# battery_monitor_6803-2_-no_uno.net
KiCad netlist of a schematic drawn in EAGLE
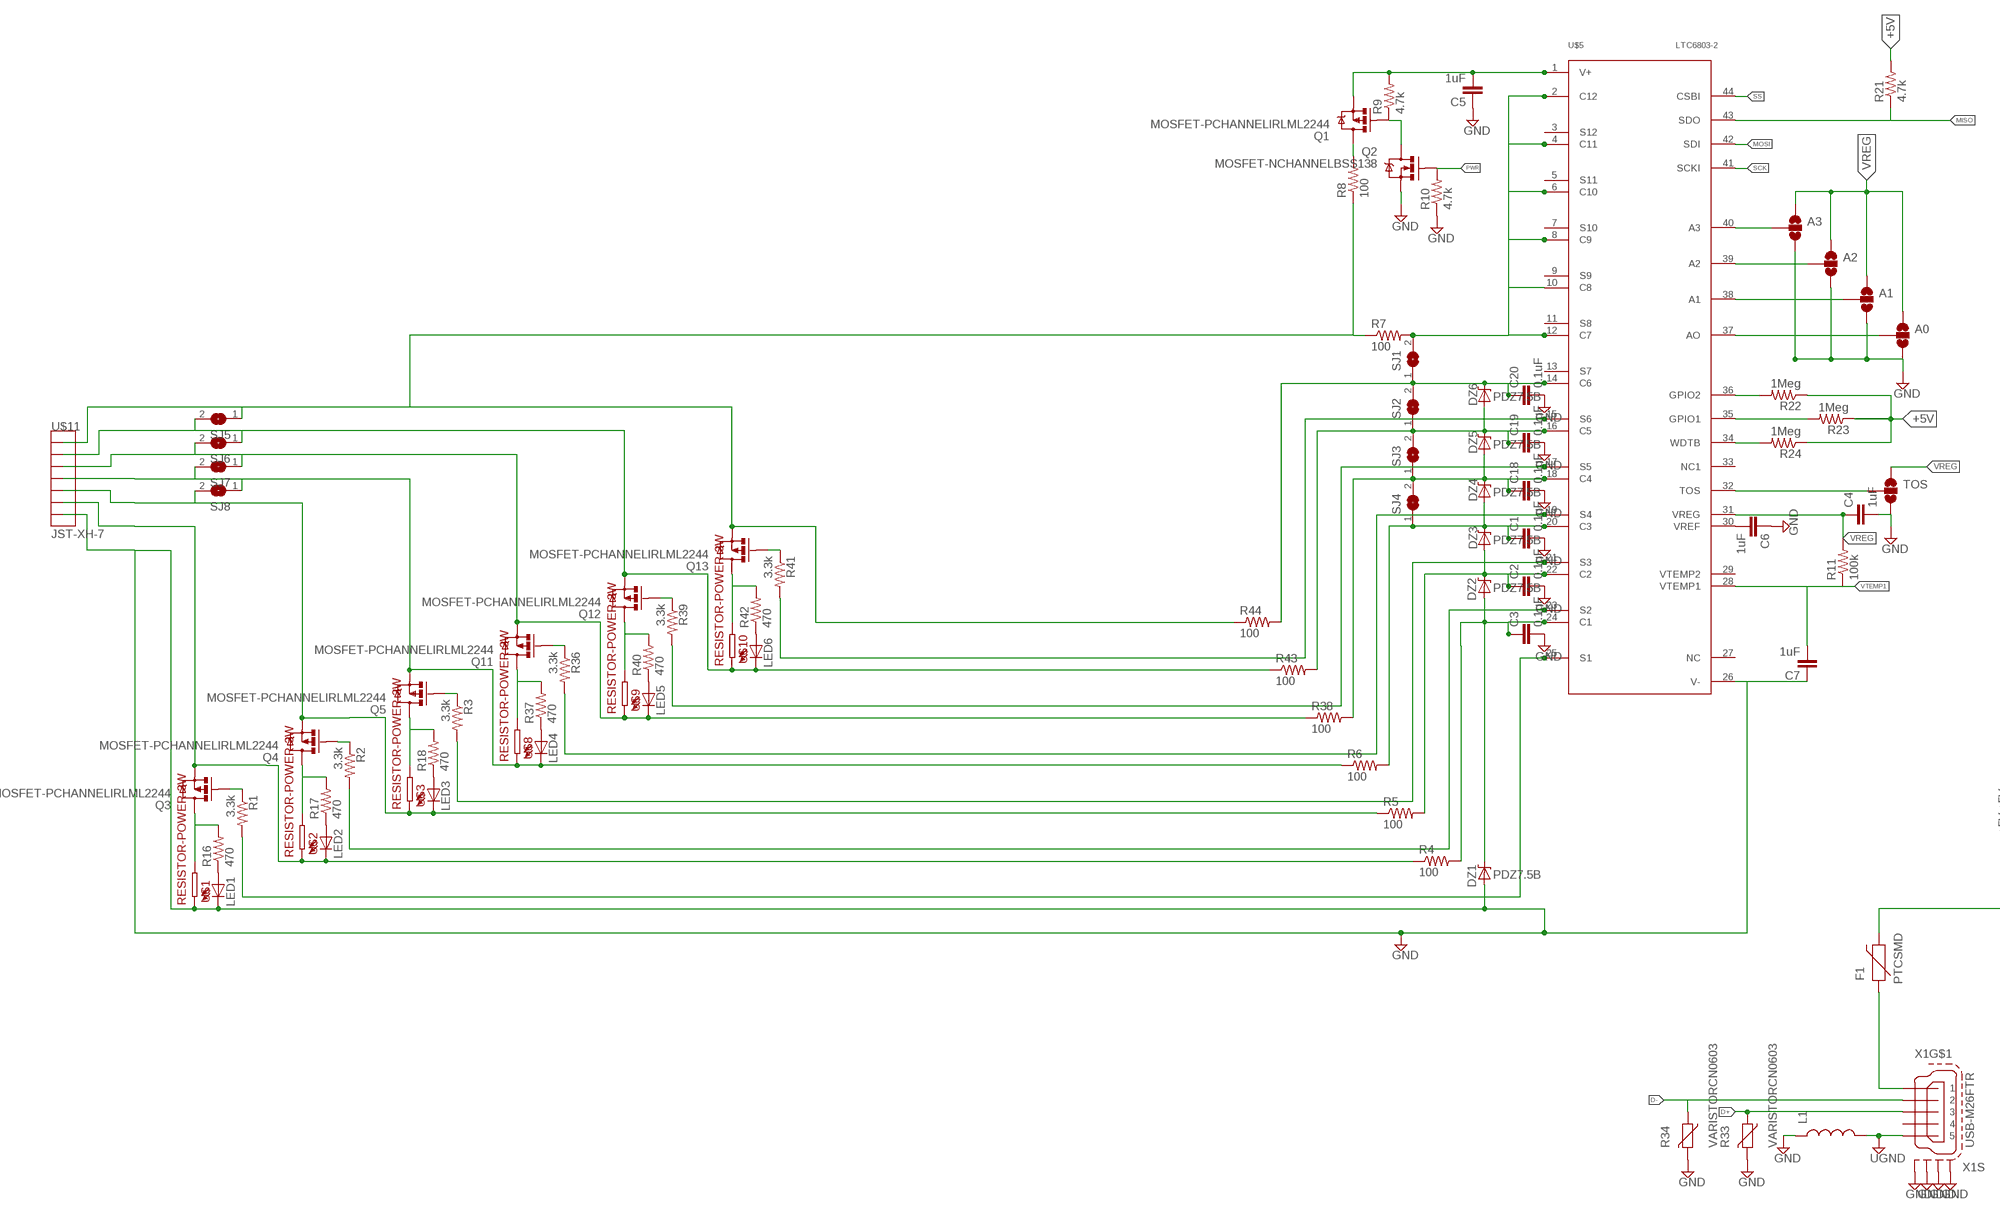
[diagram p0: schematic, sheet 1, part 1 of 2]
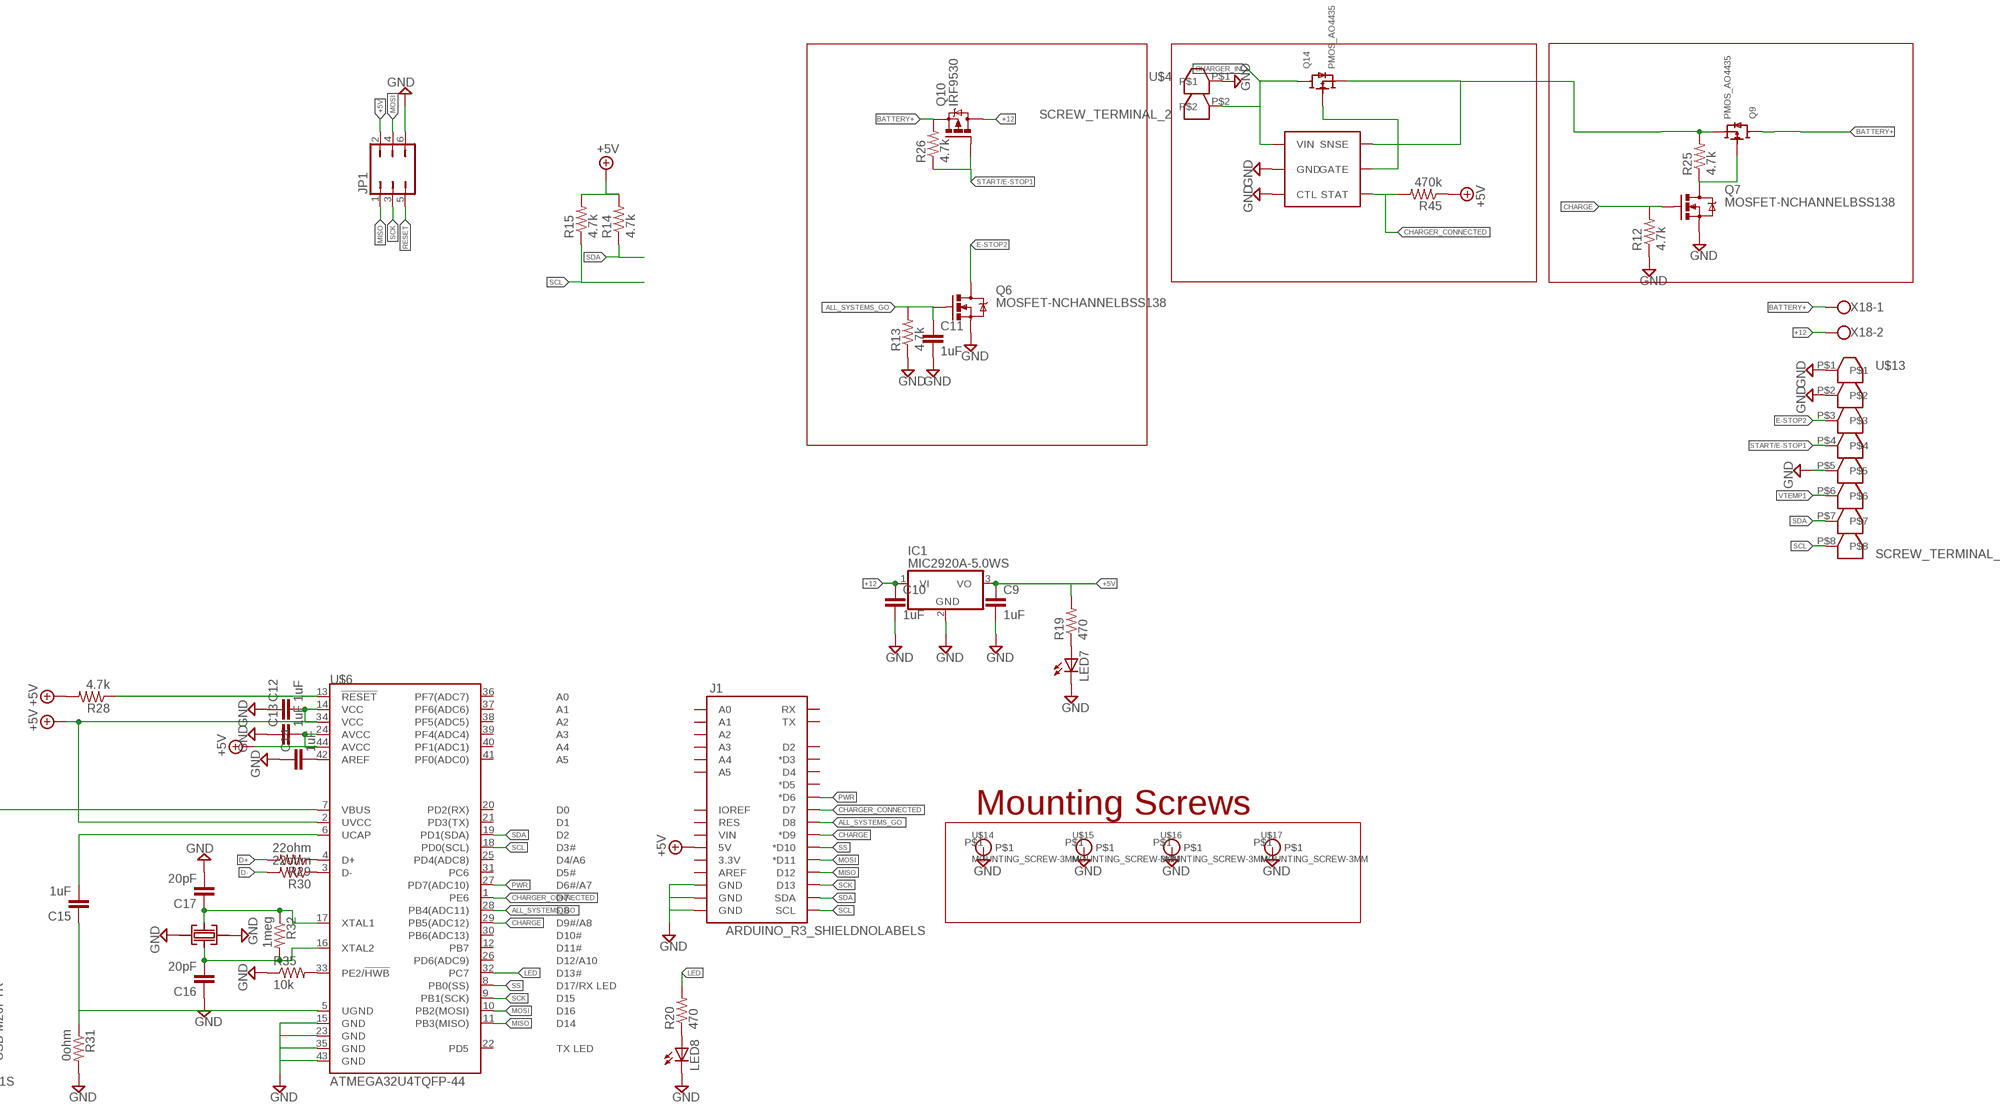
[diagram p1: schematic, sheet 1, part 2 of 2]

(export (version "E")
  (design (tool "Eeschema 10.0.6"))
  (components
    (comp (ref "A0")
      (value "SOLDERJUMPER_2WAYS")
      (footprint "eagle-import:SJ_3")
      (libsource (lib "eagle-import") (part "SOLDERJUMPER_2WAYS"))
    )
    (comp (ref "A1")
      (value "SOLDERJUMPER_2WAYS")
      (footprint "eagle-import:SJ_3")
      (libsource (lib "eagle-import") (part "SOLDERJUMPER_2WAYS"))
    )
    (comp (ref "A2")
      (value "SOLDERJUMPER_2WAYS")
      (footprint "eagle-import:SJ_3")
      (libsource (lib "eagle-import") (part "SOLDERJUMPER_2WAYS"))
    )
    (comp (ref "A3")
      (value "SOLDERJUMPER_2WAYS")
      (footprint "eagle-import:SJ_3")
      (libsource (lib "eagle-import") (part "SOLDERJUMPER_2WAYS"))
    )
    (comp (ref "C1")
      (value "0.1uF")
      (footprint "eagle-import:0603-CAP")
      (libsource (lib "eagle-import") (part "0.1UF-100V-10%(0603)"))
    )
    (comp (ref "C2")
      (value "0.1uF")
      (footprint "eagle-import:0603-CAP")
      (libsource (lib "eagle-import") (part "0.1UF-100V-10%(0603)"))
    )
    (comp (ref "C3")
      (value "0.1uF")
      (footprint "eagle-import:0603-CAP")
      (libsource (lib "eagle-import") (part "0.1UF-100V-10%(0603)"))
    )
    (comp (ref "C4")
      (value "1uF")
      (footprint "eagle-import:0603-CAP")
      (fields (field (name "PROD_ID") "CAP-08390"))
      (libsource (lib "eagle-import") (part "0.1UF-100V-10%(0603)"))
    )
    (comp (ref "C5")
      (value "1uF")
      (footprint "eagle-import:0603-CAP")
      (fields (field (name "PROD_ID") "CAP-08390"))
      (libsource (lib "eagle-import") (part "0.1UF-100V-10%(0603)"))
    )
    (comp (ref "C6")
      (value "1uF")
      (footprint "eagle-import:0603-CAP")
      (fields (field (name "PROD_ID") "CAP-08390"))
      (libsource (lib "eagle-import") (part "0.1UF-100V-10%(0603)"))
    )
    (comp (ref "C7")
      (value "1uF")
      (footprint "eagle-import:0603-CAP")
      (fields (field (name "PROD_ID") "CAP-08390"))
      (libsource (lib "eagle-import") (part "0.1UF-100V-10%(0603)"))
    )
    (comp (ref "C9")
      (value "1uF")
      (footprint "eagle-import:0603-CAP")
      (fields (field (name "PROD_ID") "CAP-08390"))
      (libsource (lib "eagle-import") (part "0.1UF-100V-10%(0603)"))
    )
    (comp (ref "C10")
      (value "1uF")
      (footprint "eagle-import:0603-CAP")
      (fields (field (name "PROD_ID") "CAP-08390"))
      (libsource (lib "eagle-import") (part "0.1UF-100V-10%(0603)"))
    )
    (comp (ref "C11")
      (value "1uF")
      (footprint "eagle-import:0603-CAP")
      (fields (field (name "PROD_ID") "CAP-08390"))
      (libsource (lib "eagle-import") (part "0.1UF-100V-10%(0603)"))
    )
    (comp (ref "C12")
      (value "1uF")
      (footprint "eagle-import:0603-CAP")
      (fields (field (name "PROD_ID") "CAP-08390"))
      (libsource (lib "eagle-import") (part "0.1UF-100V-10%(0603)"))
    )
    (comp (ref "C13")
      (value "1uF")
      (footprint "eagle-import:0603-CAP")
      (fields (field (name "PROD_ID") "CAP-08390"))
      (libsource (lib "eagle-import") (part "0.1UF-100V-10%(0603)"))
    )
    (comp (ref "C14")
      (value "1uF")
      (footprint "eagle-import:0603-CAP")
      (fields (field (name "PROD_ID") "CAP-08390"))
      (libsource (lib "eagle-import") (part "0.1UF-100V-10%(0603)"))
    )
    (comp (ref "C15")
      (value "1uF")
      (footprint "eagle-import:0603-CAP")
      (fields (field (name "PROD_ID") "CAP-08390"))
      (libsource (lib "eagle-import") (part "0.1UF-100V-10%(0603)"))
    )
    (comp (ref "C16")
      (value "20pF")
      (footprint "eagle-import:0603-CAP")
      (fields (field (name "PROD_ID") "CAP-08390"))
      (libsource (lib "eagle-import") (part "0.1UF-100V-10%(0603)"))
    )
    (comp (ref "C17")
      (value "20pF")
      (footprint "eagle-import:0603-CAP")
      (fields (field (name "PROD_ID") "CAP-08390"))
      (libsource (lib "eagle-import") (part "0.1UF-100V-10%(0603)"))
    )
    (comp (ref "C18")
      (value "0.1uF")
      (footprint "eagle-import:0603-CAP")
      (fields (field (name "PROD_ID") "CAP-08390"))
      (libsource (lib "eagle-import") (part "0.1UF-100V-10%(0603)"))
    )
    (comp (ref "C19")
      (value "0.1uF")
      (footprint "eagle-import:0603-CAP")
      (fields (field (name "PROD_ID") "CAP-08390"))
      (libsource (lib "eagle-import") (part "0.1UF-100V-10%(0603)"))
    )
    (comp (ref "C20")
      (value "0.1uF")
      (footprint "eagle-import:0603-CAP")
      (fields (field (name "PROD_ID") "CAP-08390"))
      (libsource (lib "eagle-import") (part "0.1UF-100V-10%(0603)"))
    )
    (comp (ref "DZ1")
      (value "PDZ7.5B")
      (footprint "eagle-import:SOD-323")
      (libsource (lib "eagle-import") (part "DIODE-ZENER-BZT52"))
    )
    (comp (ref "DZ2")
      (value "PDZ7.5B")
      (footprint "eagle-import:SOD-323")
      (libsource (lib "eagle-import") (part "DIODE-ZENER-BZT52"))
    )
    (comp (ref "DZ3")
      (value "PDZ7.5B")
      (footprint "eagle-import:SOD-323")
      (libsource (lib "eagle-import") (part "DIODE-ZENER-BZT52"))
    )
    (comp (ref "DZ4")
      (value "PDZ7.5B")
      (footprint "eagle-import:SOD-323")
      (libsource (lib "eagle-import") (part "DIODE-ZENER-BZT52"))
    )
    (comp (ref "DZ5")
      (value "PDZ7.5B")
      (footprint "eagle-import:SOD-323")
      (libsource (lib "eagle-import") (part "DIODE-ZENER-BZT52"))
    )
    (comp (ref "DZ6")
      (value "PDZ7.5B")
      (footprint "eagle-import:SOD-323")
      (libsource (lib "eagle-import") (part "DIODE-ZENER-BZT52"))
    )
    (comp (ref "F1")
      (value "PTCSMD")
      (footprint "eagle-import:PTC-1206")
      (libsource (lib "eagle-import") (part "PTCSMD"))
    )
    (comp (ref "IC1")
      (value "MIC2920A-5.0WS")
      (footprint "eagle-import:SOT223")
      (libsource (lib "eagle-import") (part "MCP1703DB"))
    )
    (comp (ref "J1")
      (value "ARDUINO_R3_SHIELDNOLABELS")
      (footprint "eagle-import:UNO_R3_SHIELD_NOLABELS")
      (libsource (lib "eagle-import") (part "ARDUINO_R3_SHIELDNOLABELS"))
    )
    (comp (ref "JP1")
      (value "JP3Q")
      (footprint "eagle-import:JP3Q")
      (libsource (lib "eagle-import") (part "JP3Q"))
    )
    (comp (ref "L1")
      (value "INDUCTOR0805")
      (footprint "eagle-import:0805")
      (libsource (lib "eagle-import") (part "INDUCTOR0805"))
    )
    (comp (ref "LED1")
      (value "LED0603")
      (footprint "eagle-import:LED-0603")
      (libsource (lib "eagle-import") (part "LED0603"))
    )
    (comp (ref "LED2")
      (value "LED0603")
      (footprint "eagle-import:LED-0603")
      (libsource (lib "eagle-import") (part "LED0603"))
    )
    (comp (ref "LED3")
      (value "LED0603")
      (footprint "eagle-import:LED-0603")
      (libsource (lib "eagle-import") (part "LED0603"))
    )
    (comp (ref "LED4")
      (value "LED0603")
      (footprint "eagle-import:LED-0603")
      (libsource (lib "eagle-import") (part "LED0603"))
    )
    (comp (ref "LED5")
      (value "LED0603")
      (footprint "eagle-import:LED-0603")
      (libsource (lib "eagle-import") (part "LED0603"))
    )
    (comp (ref "LED6")
      (value "LED0603")
      (footprint "eagle-import:LED-0603")
      (libsource (lib "eagle-import") (part "LED0603"))
    )
    (comp (ref "LED7")
      (value "LED0603")
      (footprint "eagle-import:LED-0603")
      (libsource (lib "eagle-import") (part "LED0603"))
    )
    (comp (ref "LED8")
      (value "LED0603")
      (footprint "eagle-import:LED-0603")
      (libsource (lib "eagle-import") (part "LED0603"))
    )
    (comp (ref "Q1")
      (value "MOSFET-PCHANNELIRLML2244")
      (footprint "eagle-import:SOT23-3")
      (libsource (lib "eagle-import") (part "MOSFET-PCHANNELIRLML2244"))
    )
    (comp (ref "Q2")
      (value "MOSFET-NCHANNELBSS138")
      (footprint "eagle-import:SOT23")
      (libsource (lib "eagle-import") (part "MOSFET-NCHANNELBSS138"))
    )
    (comp (ref "Q3")
      (value "MOSFET-PCHANNELIRLML2244")
      (footprint "eagle-import:SOT23-3")
      (libsource (lib "eagle-import") (part "MOSFET-PCHANNELIRLML2244"))
    )
    (comp (ref "Q4")
      (value "MOSFET-PCHANNELIRLML2244")
      (footprint "eagle-import:SOT23-3")
      (libsource (lib "eagle-import") (part "MOSFET-PCHANNELIRLML2244"))
    )
    (comp (ref "Q5")
      (value "MOSFET-PCHANNELIRLML2244")
      (footprint "eagle-import:SOT23-3")
      (libsource (lib "eagle-import") (part "MOSFET-PCHANNELIRLML2244"))
    )
    (comp (ref "Q6")
      (value "MOSFET-NCHANNELBSS138")
      (footprint "eagle-import:SOT23")
      (libsource (lib "eagle-import") (part "MOSFET-NCHANNELBSS138"))
    )
    (comp (ref "Q7")
      (value "MOSFET-NCHANNELBSS138")
      (footprint "eagle-import:SOT23")
      (libsource (lib "eagle-import") (part "MOSFET-NCHANNELBSS138"))
    )
    (comp (ref "Q9")
      (value "PMOS_AO4435")
      (footprint "eagle-import:SOIC8")
      (libsource (lib "eagle-import") (part "PMOS_AO4435"))
    )
    (comp (ref "Q10")
      (value "IRF9530")
      (footprint "eagle-import:TO220BV")
      (libsource (lib "eagle-import") (part "IRF9530"))
    )
    (comp (ref "Q11")
      (value "MOSFET-PCHANNELIRLML2244")
      (footprint "eagle-import:SOT23-3")
      (libsource (lib "eagle-import") (part "MOSFET-PCHANNELIRLML2244"))
    )
    (comp (ref "Q12")
      (value "MOSFET-PCHANNELIRLML2244")
      (footprint "eagle-import:SOT23-3")
      (libsource (lib "eagle-import") (part "MOSFET-PCHANNELIRLML2244"))
    )
    (comp (ref "Q13")
      (value "MOSFET-PCHANNELIRLML2244")
      (footprint "eagle-import:SOT23-3")
      (libsource (lib "eagle-import") (part "MOSFET-PCHANNELIRLML2244"))
    )
    (comp (ref "Q14")
      (value "PMOS_AO4435")
      (footprint "eagle-import:SOIC8")
      (libsource (lib "eagle-import") (part "PMOS_AO4435"))
    )
    (comp (ref "R1")
      (value "3.3k")
      (footprint "eagle-import:0603-RES")
      (libsource (lib "eagle-import") (part "3.3KOHM1/10W1%(0603)"))
    )
    (comp (ref "R2")
      (value "3.3k")
      (footprint "eagle-import:0603-RES")
      (libsource (lib "eagle-import") (part "3.3KOHM1/10W1%(0603)"))
    )
    (comp (ref "R3")
      (value "3.3k")
      (footprint "eagle-import:0603-RES")
      (libsource (lib "eagle-import") (part "3.3KOHM1/10W1%(0603)"))
    )
    (comp (ref "R4")
      (value "100")
      (footprint "eagle-import:0603-RES")
      (libsource (lib "eagle-import") (part "3.3KOHM1/10W1%(0603)"))
    )
    (comp (ref "R5")
      (value "100")
      (footprint "eagle-import:0603-RES")
      (libsource (lib "eagle-import") (part "3.3KOHM1/10W1%(0603)"))
    )
    (comp (ref "R6")
      (value "100")
      (footprint "eagle-import:0603-RES")
      (libsource (lib "eagle-import") (part "3.3KOHM1/10W1%(0603)"))
    )
    (comp (ref "R7")
      (value "100")
      (footprint "eagle-import:0603-RES")
      (libsource (lib "eagle-import") (part "3.3KOHM1/10W1%(0603)"))
    )
    (comp (ref "R8")
      (value "100")
      (footprint "eagle-import:0603-RES")
      (libsource (lib "eagle-import") (part "3.3KOHM1/10W1%(0603)"))
    )
    (comp (ref "R9")
      (value "4.7k")
      (footprint "eagle-import:0603-RES")
      (libsource (lib "eagle-import") (part "3.3KOHM1/10W1%(0603)"))
    )
    (comp (ref "R10")
      (value "4.7k")
      (footprint "eagle-import:0603-RES")
      (libsource (lib "eagle-import") (part "3.3KOHM1/10W1%(0603)"))
    )
    (comp (ref "R11")
      (value "100k")
      (footprint "eagle-import:0603-RES")
      (libsource (lib "eagle-import") (part "3.3KOHM1/10W1%(0603)"))
    )
    (comp (ref "R12")
      (value "4.7k")
      (footprint "eagle-import:0603-RES")
      (libsource (lib "eagle-import") (part "3.3KOHM1/10W1%(0603)"))
    )
    (comp (ref "R13")
      (value "4.7k")
      (footprint "eagle-import:0603-RES")
      (libsource (lib "eagle-import") (part "3.3KOHM1/10W1%(0603)"))
    )
    (comp (ref "R14")
      (value "4.7k")
      (footprint "eagle-import:0603-RES")
      (libsource (lib "eagle-import") (part "3.3KOHM1/10W1%(0603)"))
    )
    (comp (ref "R15")
      (value "4.7k")
      (footprint "eagle-import:0603-RES")
      (libsource (lib "eagle-import") (part "3.3KOHM1/10W1%(0603)"))
    )
    (comp (ref "R16")
      (value "470")
      (footprint "eagle-import:0603-RES")
      (fields (field (name "PROD_ID") "RES-07851"))
      (libsource (lib "eagle-import") (part "3.3KOHM1/10W1%(0603)"))
    )
    (comp (ref "R17")
      (value "470")
      (footprint "eagle-import:0603-RES")
      (fields (field (name "PROD_ID") "RES-07851"))
      (libsource (lib "eagle-import") (part "3.3KOHM1/10W1%(0603)"))
    )
    (comp (ref "R18")
      (value "470")
      (footprint "eagle-import:0603-RES")
      (fields (field (name "PROD_ID") "RES-07851"))
      (libsource (lib "eagle-import") (part "3.3KOHM1/10W1%(0603)"))
    )
    (comp (ref "R19")
      (value "470")
      (footprint "eagle-import:0603-RES")
      (fields (field (name "PROD_ID") "RES-07851"))
      (libsource (lib "eagle-import") (part "3.3KOHM1/10W1%(0603)"))
    )
    (comp (ref "R20")
      (value "470")
      (footprint "eagle-import:0603-RES")
      (fields (field (name "PROD_ID") "RES-07851"))
      (libsource (lib "eagle-import") (part "3.3KOHM1/10W1%(0603)"))
    )
    (comp (ref "R21")
      (value "4.7k")
      (footprint "eagle-import:0603-RES")
      (fields (field (name "PROD_ID") "RES-07851"))
      (libsource (lib "eagle-import") (part "3.3KOHM1/10W1%(0603)"))
    )
    (comp (ref "R22")
      (value "1Meg")
      (footprint "eagle-import:0603-RES")
      (fields (field (name "PROD_ID") "RES-07851"))
      (libsource (lib "eagle-import") (part "3.3KOHM1/10W1%(0603)"))
    )
    (comp (ref "R23")
      (value "1Meg")
      (footprint "eagle-import:0603-RES")
      (fields (field (name "PROD_ID") "RES-07851"))
      (libsource (lib "eagle-import") (part "3.3KOHM1/10W1%(0603)"))
    )
    (comp (ref "R24")
      (value "1Meg")
      (footprint "eagle-import:0603-RES")
      (fields (field (name "PROD_ID") "RES-07851"))
      (libsource (lib "eagle-import") (part "3.3KOHM1/10W1%(0603)"))
    )
    (comp (ref "R25")
      (value "4.7k")
      (footprint "eagle-import:0603-RES")
      (fields (field (name "PROD_ID") "RES-07851"))
      (libsource (lib "eagle-import") (part "3.3KOHM1/10W1%(0603)"))
    )
    (comp (ref "R26")
      (value "4.7k")
      (footprint "eagle-import:0603-RES")
      (fields (field (name "PROD_ID") "RES-07851"))
      (libsource (lib "eagle-import") (part "3.3KOHM1/10W1%(0603)"))
    )
    (comp (ref "R28")
      (value "4.7k")
      (footprint "eagle-import:0603-RES")
      (fields (field (name "PROD_ID") "RES-07851"))
      (libsource (lib "eagle-import") (part "3.3KOHM1/10W1%(0603)"))
    )
    (comp (ref "R29")
      (value "22ohm")
      (footprint "eagle-import:0603-RES")
      (fields (field (name "PROD_ID") "RES-07851"))
      (libsource (lib "eagle-import") (part "3.3KOHM1/10W1%(0603)"))
    )
    (comp (ref "R30")
      (value "22ohm")
      (footprint "eagle-import:0603-RES")
      (fields (field (name "PROD_ID") "RES-07851"))
      (libsource (lib "eagle-import") (part "3.3KOHM1/10W1%(0603)"))
    )
    (comp (ref "R31")
      (value "0ohm")
      (footprint "eagle-import:0603-RES")
      (fields (field (name "PROD_ID") "RES-07851"))
      (libsource (lib "eagle-import") (part "3.3KOHM1/10W1%(0603)"))
    )
    (comp (ref "R32")
      (value "1meg")
      (footprint "eagle-import:0603-RES")
      (fields (field (name "PROD_ID") "RES-07851"))
      (libsource (lib "eagle-import") (part "3.3KOHM1/10W1%(0603)"))
    )
    (comp (ref "R33")
      (value "VARISTORCN0603")
      (footprint "eagle-import:CT_CN0603")
      (libsource (lib "eagle-import") (part "VARISTORCN0603"))
    )
    (comp (ref "R34")
      (value "VARISTORCN0603")
      (footprint "eagle-import:CT_CN0603")
      (libsource (lib "eagle-import") (part "VARISTORCN0603"))
    )
    (comp (ref "R35")
      (value "10k")
      (footprint "eagle-import:0603-RES")
      (fields (field (name "PROD_ID") "RES-07851"))
      (libsource (lib "eagle-import") (part "3.3KOHM1/10W1%(0603)"))
    )
    (comp (ref "R36")
      (value "3.3k")
      (footprint "eagle-import:0603-RES")
      (libsource (lib "eagle-import") (part "3.3KOHM1/10W1%(0603)"))
    )
    (comp (ref "R37")
      (value "470")
      (footprint "eagle-import:0603-RES")
      (fields (field (name "PROD_ID") "RES-07851"))
      (libsource (lib "eagle-import") (part "3.3KOHM1/10W1%(0603)"))
    )
    (comp (ref "R38")
      (value "100")
      (footprint "eagle-import:0603-RES")
      (fields (field (name "PROD_ID") "RES-07851"))
      (libsource (lib "eagle-import") (part "3.3KOHM1/10W1%(0603)"))
    )
    (comp (ref "R39")
      (value "3.3k")
      (footprint "eagle-import:0603-RES")
      (libsource (lib "eagle-import") (part "3.3KOHM1/10W1%(0603)"))
    )
    (comp (ref "R40")
      (value "470")
      (footprint "eagle-import:0603-RES")
      (fields (field (name "PROD_ID") "RES-07851"))
      (libsource (lib "eagle-import") (part "3.3KOHM1/10W1%(0603)"))
    )
    (comp (ref "R41")
      (value "3.3k")
      (footprint "eagle-import:0603-RES")
      (libsource (lib "eagle-import") (part "3.3KOHM1/10W1%(0603)"))
    )
    (comp (ref "R42")
      (value "470")
      (footprint "eagle-import:0603-RES")
      (fields (field (name "PROD_ID") "RES-07851"))
      (libsource (lib "eagle-import") (part "3.3KOHM1/10W1%(0603)"))
    )
    (comp (ref "R43")
      (value "100")
      (footprint "eagle-import:0603-RES")
      (fields (field (name "PROD_ID") "RES-07851"))
      (libsource (lib "eagle-import") (part "3.3KOHM1/10W1%(0603)"))
    )
    (comp (ref "R44")
      (value "100")
      (footprint "eagle-import:0603-RES")
      (fields (field (name "PROD_ID") "RES-07851"))
      (libsource (lib "eagle-import") (part "3.3KOHM1/10W1%(0603)"))
    )
    (comp (ref "R45")
      (value "470k")
      (footprint "eagle-import:0603-RES")
      (fields (field (name "PROD_ID") "RES-07851"))
      (libsource (lib "eagle-import") (part "3.3KOHM1/10W1%(0603)"))
    )
    (comp (ref "SJ1") (value "SJ") (footprint "eagle-import:SJ") (libsource (lib "eagle-import") (part "SJ")))
    (comp (ref "SJ2") (value "SJ") (footprint "eagle-import:SJ") (libsource (lib "eagle-import") (part "SJ")))
    (comp (ref "SJ3") (value "SJ") (footprint "eagle-import:SJ") (libsource (lib "eagle-import") (part "SJ")))
    (comp (ref "SJ4") (value "SJ") (footprint "eagle-import:SJ") (libsource (lib "eagle-import") (part "SJ")))
    (comp (ref "SJ5") (value "SJ") (footprint "eagle-import:SJ") (libsource (lib "eagle-import") (part "SJ")))
    (comp (ref "SJ6") (value "SJ") (footprint "eagle-import:SJ") (libsource (lib "eagle-import") (part "SJ")))
    (comp (ref "SJ7") (value "SJ") (footprint "eagle-import:SJ") (libsource (lib "eagle-import") (part "SJ")))
    (comp (ref "SJ8") (value "SJ") (footprint "eagle-import:SJ") (libsource (lib "eagle-import") (part "SJ")))
    (comp (ref "TOS")
      (value "SOLDERJUMPER_2WAYS")
      (footprint "eagle-import:SJ_3")
      (libsource (lib "eagle-import") (part "SOLDERJUMPER_2WAYS"))
    )
    (comp (ref "U$1")
      (value "RESISTOR-POWER-3W")
      (footprint "eagle-import:RESISTOR-3W")
      (libsource (lib "eagle-import") (part "RESISTOR-POWER-3W"))
    )
    (comp (ref "U$2")
      (value "RESISTOR-POWER-3W")
      (footprint "eagle-import:RESISTOR-3W")
      (libsource (lib "eagle-import") (part "RESISTOR-POWER-3W"))
    )
    (comp (ref "U$3")
      (value "RESISTOR-POWER-3W")
      (footprint "eagle-import:RESISTOR-3W")
      (libsource (lib "eagle-import") (part "RESISTOR-POWER-3W"))
    )
    (comp (ref "U$4")
      (value "SCREW_TERMINAL_2")
      (footprint "eagle-import:SCREW_TERMINAL_2")
      (libsource (lib "eagle-import") (part "SCREW_TERMINAL_2"))
    )
    (comp (ref "U$5")
      (value "LTC6803-2")
      (footprint "eagle-import:FSOP-44")
      (libsource (lib "eagle-import") (part "LTC6803-2"))
    )
    (comp (ref "U$6")
      (value "ATMEGA32U4TQFP-44")
      (footprint "eagle-import:TQFP44")
      (libsource (lib "eagle-import") (part "ATMEGA32U4TQFP-44"))
    )
    (comp (ref "U$7")
      (value "CRYSTAL_403")
      (footprint "eagle-import:CRYSTAL(DFN,LCC)")
      (libsource (lib "eagle-import") (part "CRYSTAL_403"))
    )
    (comp (ref "U$8")
      (value "RESISTOR-POWER-3W")
      (footprint "eagle-import:RESISTOR-3W")
      (libsource (lib "eagle-import") (part "RESISTOR-POWER-3W"))
    )
    (comp (ref "U$9")
      (value "RESISTOR-POWER-3W")
      (footprint "eagle-import:RESISTOR-3W")
      (libsource (lib "eagle-import") (part "RESISTOR-POWER-3W"))
    )
    (comp (ref "U$10")
      (value "RESISTOR-POWER-3W")
      (footprint "eagle-import:RESISTOR-3W")
      (libsource (lib "eagle-import") (part "RESISTOR-POWER-3W"))
    )
    (comp (ref "U$11")
      (value "JST-XH-7")
      (footprint "eagle-import:JST-XH-7")
      (libsource (lib "eagle-import") (part "JST-XH-7"))
    )
    (comp (ref "U$12")
      (value "LTC4412")
      (footprint "eagle-import:SOT-23-6")
      (libsource (lib "eagle-import") (part "LTC4412"))
    )
    (comp (ref "U$13")
      (value "SCREW_TERMINAL_8")
      (footprint "eagle-import:SCREW_TERMINAL_8")
      (libsource (lib "eagle-import") (part "SCREW_TERMINAL_8"))
    )
    (comp (ref "U$14")
      (value "MOUNTING_SCREW-3MM")
      (footprint "eagle-import:MOUNTING_SCREW-3MM")
      (libsource (lib "eagle-import") (part "MOUNTING_SCREW-3MM"))
    )
    (comp (ref "U$15")
      (value "MOUNTING_SCREW-3MM")
      (footprint "eagle-import:MOUNTING_SCREW-3MM")
      (libsource (lib "eagle-import") (part "MOUNTING_SCREW-3MM"))
    )
    (comp (ref "U$16")
      (value "MOUNTING_SCREW-3MM")
      (footprint "eagle-import:MOUNTING_SCREW-3MM")
      (libsource (lib "eagle-import") (part "MOUNTING_SCREW-3MM"))
    )
    (comp (ref "U$17")
      (value "MOUNTING_SCREW-3MM")
      (footprint "eagle-import:MOUNTING_SCREW-3MM")
      (libsource (lib "eagle-import") (part "MOUNTING_SCREW-3MM"))
    )
    (comp (ref "X1")
      (value "USB-M26FTR")
      (footprint "eagle-import:32005-301")
      (libsource (lib "eagle-import") (part "MINI-USB-SCHIELD-32005-301"))
    )
    (comp (ref "X18")
      (value "W237-102")
      (footprint "eagle-import:W237-102")
      (fields (field (name "MPN") "237-102"))
      (libsource (lib "eagle-import") (part "W237-102"))
    )
  )
  (nets
    (net (code "1") (name "+5V") (class "Default")
      (node (ref "C12") (pin "2") (pinfunction "2_2") (pintype "passive"))
      (node (ref "C13") (pin "2") (pinfunction "2_2") (pintype "passive"))
      (node (ref "C9") (pin "1") (pinfunction "1_1") (pintype "passive"))
      (node (ref "IC1") (pin "3") (pinfunction "VO_3") (pintype "passive"))
      (node (ref "J1") (pin "5V") (pinfunction "5V_5V") (pintype "bidirectional"))
      (node (ref "JP1") (pin "2") (pinfunction "2_2") (pintype "passive"))
      (node (ref "R14") (pin "2") (pinfunction "2_2") (pintype "passive"))
      (node (ref "R15") (pin "2") (pinfunction "2_2") (pintype "passive"))
      (node (ref "R19") (pin "2") (pinfunction "2_2") (pintype "passive"))
      (node (ref "R21") (pin "2") (pinfunction "2_2") (pintype "passive"))
      (node (ref "R22") (pin "1") (pinfunction "1_1") (pintype "passive"))
      (node (ref "R23") (pin "1") (pinfunction "1_1") (pintype "passive"))
      (node (ref "R24") (pin "1") (pinfunction "1_1") (pintype "passive"))
      (node (ref "R28") (pin "2") (pinfunction "2_2") (pintype "passive"))
      (node (ref "R45") (pin "1") (pinfunction "1_1") (pintype "passive"))
      (node (ref "U$6") (pin "14") (pinfunction "VCC_14") (pintype "bidirectional"))
      (node (ref "U$6") (pin "2") (pinfunction "UVCC_2") (pintype "bidirectional"))
      (node (ref "U$6") (pin "24") (pinfunction "AVCC_24") (pintype "bidirectional"))
      (node (ref "U$6") (pin "34") (pinfunction "VCC_34") (pintype "bidirectional"))
      (node (ref "U$6") (pin "44") (pinfunction "AVCC_44") (pintype "bidirectional"))
    )
    (net (code "2") (name "+12") (class "Default")
      (node (ref "C10") (pin "1") (pinfunction "1_1") (pintype "passive"))
      (node (ref "IC1") (pin "1") (pinfunction "VI_1") (pintype "input"))
      (node (ref "Q10") (pin "D") (pinfunction "D_D") (pintype "passive"))
      (node (ref "X18") (pin "2") (pinfunction "KL_2") (pintype "passive"))
    )
    (net (code "3") (name "ALL_SYSTEMS_GO") (class "Default")
      (node (ref "C11") (pin "1") (pinfunction "1_1") (pintype "passive"))
      (node (ref "J1") (pin "D8") (pinfunction "D8_D8") (pintype "bidirectional"))
      (node (ref "Q6") (pin "1") (pinfunction "G_1") (pintype "passive"))
      (node (ref "R13") (pin "2") (pinfunction "2_2") (pintype "passive"))
      (node (ref "U$6") (pin "28") (pinfunction "PB4(ADC11)_28") (pintype "bidirectional"))
    )
    (net (code "4") (name "BATTERY+") (class "Default")
      (node (ref "Q10") (pin "S") (pinfunction "S_S") (pintype "passive"))
      (node (ref "Q9") (pin "5") (pinfunction "DRAIN_5") (pintype "bidirectional"))
      (node (ref "Q9") (pin "6") (pinfunction "DRAIN_6") (pintype "bidirectional"))
      (node (ref "Q9") (pin "7") (pinfunction "DRAIN_7") (pintype "bidirectional"))
      (node (ref "Q9") (pin "8") (pinfunction "DRAIN_8") (pintype "bidirectional"))
      (node (ref "R26") (pin "2") (pinfunction "2_2") (pintype "passive"))
      (node (ref "X18") (pin "1") (pinfunction "KL_1") (pintype "passive"))
    )
    (net (code "5") (name "CHARGE") (class "Default")
      (node (ref "J1") (pin "D9") (pinfunction "*D9_D9") (pintype "bidirectional"))
      (node (ref "Q7") (pin "1") (pinfunction "G_1") (pintype "passive"))
      (node (ref "R12") (pin "2") (pinfunction "2_2") (pintype "passive"))
      (node (ref "U$6") (pin "29") (pinfunction "PB5(ADC12)_29") (pintype "bidirectional"))
    )
    (net (code "6") (name "CHARGER_CONNECTED") (class "Default")
      (node (ref "J1") (pin "D7") (pinfunction "D7_D7") (pintype "bidirectional"))
      (node (ref "R45") (pin "2") (pinfunction "2_2") (pintype "passive"))
      (node (ref "U$12") (pin "P$4") (pinfunction "STAT_P$4") (pintype "bidirectional"))
      (node (ref "U$6") (pin "1") (pinfunction "PE6_1") (pintype "bidirectional"))
    )
    (net (code "7") (name "CHARGER_IN") (class "Default")
      (node (ref "Q14") (pin "5") (pinfunction "DRAIN_5") (pintype "bidirectional"))
      (node (ref "Q14") (pin "6") (pinfunction "DRAIN_6") (pintype "bidirectional"))
      (node (ref "Q14") (pin "7") (pinfunction "DRAIN_7") (pintype "bidirectional"))
      (node (ref "Q14") (pin "8") (pinfunction "DRAIN_8") (pintype "bidirectional"))
      (node (ref "U$12") (pin "P$1") (pinfunction "VIN_P$1") (pintype "bidirectional"))
      (node (ref "U$4") (pin "P$2") (pinfunction "P$2_P$2") (pintype "bidirectional"))
    )
    (net (code "8") (name "D+") (class "Default")
      (node (ref "R29") (pin "2") (pinfunction "2_2") (pintype "passive"))
      (node (ref "R33") (pin "1") (pinfunction "1_1") (pintype "passive"))
      (node (ref "X1") (pin "3") (pinfunction "3_3") (pintype "passive"))
    )
    (net (code "9") (name "D-") (class "Default")
      (node (ref "R30") (pin "2") (pinfunction "2_2") (pintype "passive"))
      (node (ref "R34") (pin "1") (pinfunction "1_1") (pintype "passive"))
      (node (ref "X1") (pin "2") (pinfunction "2_2") (pintype "passive"))
    )
    (net (code "10") (name "E-STOP2") (class "Default")
      (node (ref "Q6") (pin "3") (pinfunction "D_3") (pintype "passive"))
      (node (ref "U$13") (pin "P$3") (pinfunction "P$3_P$3") (pintype "bidirectional"))
    )
    (net (code "11") (name "GND") (class "Default")
      (node (ref "A0") (pin "3") (pinfunction "3_3") (pintype "passive"))
      (node (ref "A1") (pin "3") (pinfunction "3_3") (pintype "passive"))
      (node (ref "A2") (pin "3") (pinfunction "3_3") (pintype "passive"))
      (node (ref "A3") (pin "3") (pinfunction "3_3") (pintype "passive"))
      (node (ref "C1") (pin "2") (pinfunction "2_2") (pintype "passive"))
      (node (ref "C10") (pin "2") (pinfunction "2_2") (pintype "passive"))
      (node (ref "C11") (pin "2") (pinfunction "2_2") (pintype "passive"))
      (node (ref "C12") (pin "1") (pinfunction "1_1") (pintype "passive"))
      (node (ref "C13") (pin "1") (pinfunction "1_1") (pintype "passive"))
      (node (ref "C14") (pin "1") (pinfunction "1_1") (pintype "passive"))
      (node (ref "C16") (pin "1") (pinfunction "1_1") (pintype "passive"))
      (node (ref "C17") (pin "2") (pinfunction "2_2") (pintype "passive"))
      (node (ref "C18") (pin "2") (pinfunction "2_2") (pintype "passive"))
      (node (ref "C19") (pin "2") (pinfunction "2_2") (pintype "passive"))
      (node (ref "C2") (pin "2") (pinfunction "2_2") (pintype "passive"))
      (node (ref "C20") (pin "2") (pinfunction "2_2") (pintype "passive"))
      (node (ref "C3") (pin "2") (pinfunction "2_2") (pintype "passive"))
      (node (ref "C4") (pin "2") (pinfunction "2_2") (pintype "passive"))
      (node (ref "C5") (pin "1") (pinfunction "1_1") (pintype "passive"))
      (node (ref "C6") (pin "1") (pinfunction "1_1") (pintype "passive"))
      (node (ref "C7") (pin "1") (pinfunction "1_1") (pintype "passive"))
      (node (ref "C9") (pin "2") (pinfunction "2_2") (pintype "passive"))
      (node (ref "DZ1") (pin "2") (pinfunction "A_2") (pintype "passive"))
      (node (ref "IC1") (pin "2") (pinfunction "GND_2") (pintype "passive"))
      (node (ref "J1") (pin "GND@0") (pinfunction "GND_GND@0") (pintype "bidirectional"))
      (node (ref "J1") (pin "GND@1") (pinfunction "GND_GND@1") (pintype "bidirectional"))
      (node (ref "J1") (pin "GND@2") (pinfunction "GND_GND@2") (pintype "bidirectional"))
      (node (ref "JP1") (pin "6") (pinfunction "6_6") (pintype "passive"))
      (node (ref "L1") (pin "1") (pinfunction "1_1") (pintype "passive"))
      (node (ref "LED1") (pin "C") (pinfunction "C_C") (pintype "passive"))
      (node (ref "LED7") (pin "C") (pinfunction "C_C") (pintype "passive"))
      (node (ref "LED8") (pin "C") (pinfunction "C_C") (pintype "passive"))
      (node (ref "Q2") (pin "2") (pinfunction "S_2") (pintype "passive"))
      (node (ref "Q6") (pin "2") (pinfunction "S_2") (pintype "passive"))
      (node (ref "Q7") (pin "2") (pinfunction "S_2") (pintype "passive"))
      (node (ref "R10") (pin "1") (pinfunction "1_1") (pintype "passive"))
      (node (ref "R12") (pin "1") (pinfunction "1_1") (pintype "passive"))
      (node (ref "R13") (pin "1") (pinfunction "1_1") (pintype "passive"))
      (node (ref "R31") (pin "2") (pinfunction "2_2") (pintype "passive"))
      (node (ref "R33") (pin "2") (pinfunction "2_2") (pintype "passive"))
      (node (ref "R34") (pin "2") (pinfunction "2_2") (pintype "passive"))
      (node (ref "R35") (pin "1") (pinfunction "1_1") (pintype "passive"))
      (node (ref "TOS") (pin "3") (pinfunction "3_3") (pintype "passive"))
      (node (ref "U$1") (pin "P$2") (pinfunction "P$2_P$2") (pintype "bidirectional"))
      (node (ref "U$11") (pin "1") (pinfunction "1_1") (pintype "bidirectional"))
      (node (ref "U$12") (pin "P$2") (pinfunction "GND_P$2") (pintype "bidirectional"))
      (node (ref "U$12") (pin "P$3") (pinfunction "CTL_P$3") (pintype "bidirectional"))
      (node (ref "U$13") (pin "P$1") (pinfunction "P$1_P$1") (pintype "bidirectional"))
      (node (ref "U$13") (pin "P$2") (pinfunction "P$2_P$2") (pintype "bidirectional"))
      (node (ref "U$13") (pin "P$5") (pinfunction "P$5_P$5") (pintype "bidirectional"))
      (node (ref "U$14") (pin "P$1") (pinfunction "P$1_P$1") (pintype "bidirectional"))
      (node (ref "U$15") (pin "P$1") (pinfunction "P$1_P$1") (pintype "bidirectional"))
      (node (ref "U$16") (pin "P$1") (pinfunction "P$1_P$1") (pintype "bidirectional"))
      (node (ref "U$17") (pin "P$1") (pinfunction "P$1_P$1") (pintype "bidirectional"))
      (node (ref "U$4") (pin "P$1") (pinfunction "P$1_P$1") (pintype "bidirectional"))
      (node (ref "U$5") (pin "26") (pinfunction "V-_26") (pintype "bidirectional"))
      (node (ref "U$6") (pin "15") (pinfunction "GND_15") (pintype "bidirectional"))
      (node (ref "U$6") (pin "23") (pinfunction "GND_23") (pintype "bidirectional"))
      (node (ref "U$6") (pin "35") (pinfunction "GND_35") (pintype "bidirectional"))
      (node (ref "U$6") (pin "43") (pinfunction "GND_43") (pintype "bidirectional"))
      (node (ref "U$7") (pin "CASE") (pinfunction "CASE_CASE") (pintype "bidirectional"))
      (node (ref "U$7") (pin "CASE1") (pinfunction "CASE1_CASE1") (pintype "bidirectional"))
      (node (ref "X1") (pin "M1") (pinfunction "S1_M1") (pintype "passive"))
      (node (ref "X1") (pin "M2") (pinfunction "S2_M2") (pintype "passive"))
      (node (ref "X1") (pin "M3") (pinfunction "S3_M3") (pintype "passive"))
      (node (ref "X1") (pin "M4") (pinfunction "S4_M4") (pintype "passive"))
    )
    (net (code "12") (name "LED") (class "Default")
      (node (ref "R20") (pin "2") (pinfunction "2_2") (pintype "passive"))
      (node (ref "U$6") (pin "32") (pinfunction "PC7_32") (pintype "bidirectional"))
    )
    (net (code "13") (name "MISO") (class "Default")
      (node (ref "J1") (pin "D12") (pinfunction "D12_D12") (pintype "bidirectional"))
      (node (ref "JP1") (pin "1") (pinfunction "1_1") (pintype "passive"))
      (node (ref "R21") (pin "1") (pinfunction "1_1") (pintype "passive"))
      (node (ref "U$5") (pin "43") (pinfunction "SDO_43") (pintype "bidirectional"))
      (node (ref "U$6") (pin "11") (pinfunction "PB3(MISO)_11") (pintype "bidirectional"))
    )
    (net (code "14") (name "MOSI") (class "Default")
      (node (ref "J1") (pin "D11") (pinfunction "*D11_D11") (pintype "bidirectional"))
      (node (ref "JP1") (pin "4") (pinfunction "4_4") (pintype "passive"))
      (node (ref "U$5") (pin "42") (pinfunction "SDI_42") (pintype "bidirectional"))
      (node (ref "U$6") (pin "10") (pinfunction "PB2(MOSI)_10") (pintype "bidirectional"))
    )
    (net (code "15") (name "Net-(DZ1-C)") (class "Default")
      (node (ref "C3") (pin "1") (pinfunction "1_1") (pintype "passive"))
      (node (ref "DZ1") (pin "1") (pinfunction "C_1") (pintype "passive"))
      (node (ref "DZ2") (pin "2") (pinfunction "A_2") (pintype "passive"))
      (node (ref "R4") (pin "2") (pinfunction "2_2") (pintype "passive"))
      (node (ref "U$5") (pin "24") (pinfunction "C1_24") (pintype "bidirectional"))
    )
    (net (code "16") (name "Net-(DZ2-C)") (class "Default")
      (node (ref "C2") (pin "1") (pinfunction "1_1") (pintype "passive"))
      (node (ref "DZ2") (pin "1") (pinfunction "C_1") (pintype "passive"))
      (node (ref "DZ3") (pin "2") (pinfunction "A_2") (pintype "passive"))
      (node (ref "R5") (pin "2") (pinfunction "2_2") (pintype "passive"))
      (node (ref "U$5") (pin "22") (pinfunction "C2_22") (pintype "bidirectional"))
    )
    (net (code "17") (name "Net-(DZ3-C)") (class "Default")
      (node (ref "C1") (pin "1") (pinfunction "1_1") (pintype "passive"))
      (node (ref "DZ3") (pin "1") (pinfunction "C_1") (pintype "passive"))
      (node (ref "DZ4") (pin "2") (pinfunction "A_2") (pintype "passive"))
      (node (ref "R6") (pin "2") (pinfunction "2_2") (pintype "passive"))
      (node (ref "SJ4") (pin "1") (pinfunction "1_1") (pintype "passive"))
      (node (ref "U$5") (pin "20") (pinfunction "C3_20") (pintype "bidirectional"))
    )
    (net (code "18") (name "Net-(DZ4-C)") (class "Default")
      (node (ref "C18") (pin "1") (pinfunction "1_1") (pintype "passive"))
      (node (ref "DZ4") (pin "1") (pinfunction "C_1") (pintype "passive"))
      (node (ref "DZ5") (pin "2") (pinfunction "A_2") (pintype "passive"))
      (node (ref "R38") (pin "2") (pinfunction "2_2") (pintype "passive"))
      (node (ref "SJ3") (pin "1") (pinfunction "1_1") (pintype "passive"))
      (node (ref "SJ4") (pin "2") (pinfunction "2_2") (pintype "passive"))
      (node (ref "U$5") (pin "18") (pinfunction "C4_18") (pintype "bidirectional"))
    )
    (net (code "19") (name "Net-(DZ5-C)") (class "Default")
      (node (ref "C19") (pin "1") (pinfunction "1_1") (pintype "passive"))
      (node (ref "DZ5") (pin "1") (pinfunction "C_1") (pintype "passive"))
      (node (ref "DZ6") (pin "2") (pinfunction "A_2") (pintype "passive"))
      (node (ref "R43") (pin "2") (pinfunction "2_2") (pintype "passive"))
      (node (ref "SJ2") (pin "1") (pinfunction "1_1") (pintype "passive"))
      (node (ref "SJ3") (pin "2") (pinfunction "2_2") (pintype "passive"))
      (node (ref "U$5") (pin "16") (pinfunction "C5_16") (pintype "bidirectional"))
    )
    (net (code "20") (name "Net-(DZ6-C)") (class "Default")
      (node (ref "C20") (pin "1") (pinfunction "1_1") (pintype "passive"))
      (node (ref "DZ6") (pin "1") (pinfunction "C_1") (pintype "passive"))
      (node (ref "R44") (pin "2") (pinfunction "2_2") (pintype "passive"))
      (node (ref "SJ1") (pin "1") (pinfunction "1_1") (pintype "passive"))
      (node (ref "SJ2") (pin "2") (pinfunction "2_2") (pintype "passive"))
      (node (ref "U$5") (pin "14") (pinfunction "C6_14") (pintype "bidirectional"))
    )
    (net (code "21") (name "Net-(F1-Pad1)") (class "Default")
      (node (ref "F1") (pin "1") (pinfunction "1_1") (pintype "bidirectional"))
      (node (ref "X1") (pin "1") (pinfunction "1_1") (pintype "passive"))
    )
    (net (code "22") (name "Net-(LED1-PadA)") (class "Default")
      (node (ref "LED1") (pin "A") (pinfunction "A_A") (pintype "passive"))
      (node (ref "R16") (pin "1") (pinfunction "1_1") (pintype "passive"))
    )
    (net (code "23") (name "Net-(LED2-PadA)") (class "Default")
      (node (ref "LED2") (pin "A") (pinfunction "A_A") (pintype "passive"))
      (node (ref "R17") (pin "1") (pinfunction "1_1") (pintype "passive"))
    )
    (net (code "24") (name "Net-(LED3-PadA)") (class "Default")
      (node (ref "LED3") (pin "A") (pinfunction "A_A") (pintype "passive"))
      (node (ref "R18") (pin "1") (pinfunction "1_1") (pintype "passive"))
    )
    (net (code "25") (name "Net-(LED4-PadA)") (class "Default")
      (node (ref "LED4") (pin "A") (pinfunction "A_A") (pintype "passive"))
      (node (ref "R37") (pin "1") (pinfunction "1_1") (pintype "passive"))
    )
    (net (code "26") (name "Net-(LED5-PadA)") (class "Default")
      (node (ref "LED5") (pin "A") (pinfunction "A_A") (pintype "passive"))
      (node (ref "R40") (pin "1") (pinfunction "1_1") (pintype "passive"))
    )
    (net (code "27") (name "Net-(LED6-PadA)") (class "Default")
      (node (ref "LED6") (pin "A") (pinfunction "A_A") (pintype "passive"))
      (node (ref "R42") (pin "1") (pinfunction "1_1") (pintype "passive"))
    )
    (net (code "28") (name "Net-(LED7-PadA)") (class "Default")
      (node (ref "LED7") (pin "A") (pinfunction "A_A") (pintype "passive"))
      (node (ref "R19") (pin "1") (pinfunction "1_1") (pintype "passive"))
    )
    (net (code "29") (name "Net-(LED8-PadA)") (class "Default")
      (node (ref "LED8") (pin "A") (pinfunction "A_A") (pintype "passive"))
      (node (ref "R20") (pin "1") (pinfunction "1_1") (pintype "passive"))
    )
    (net (code "30") (name "Net-(Q1-D)") (class "Default")
      (node (ref "Q1") (pin "3") (pinfunction "D_3") (pintype "passive"))
      (node (ref "R8") (pin "2") (pinfunction "2_2") (pintype "passive"))
    )
    (net (code "31") (name "Net-(Q1-G)") (class "Default")
      (node (ref "Q1") (pin "1") (pinfunction "G_1") (pintype "passive"))
      (node (ref "Q2") (pin "3") (pinfunction "D_3") (pintype "passive"))
      (node (ref "R9") (pin "1") (pinfunction "1_1") (pintype "passive"))
    )
    (net (code "32") (name "Net-(Q1-S)") (class "Default")
      (node (ref "C5") (pin "2") (pinfunction "2_2") (pintype "passive"))
      (node (ref "Q1") (pin "2") (pinfunction "S_2") (pintype "passive"))
      (node (ref "R9") (pin "2") (pinfunction "2_2") (pintype "passive"))
      (node (ref "U$5") (pin "1") (pinfunction "V+_1") (pintype "bidirectional"))
    )
    (net (code "33") (name "Net-(Q3-D)") (class "Default")
      (node (ref "Q3") (pin "3") (pinfunction "D_3") (pintype "passive"))
      (node (ref "R16") (pin "2") (pinfunction "2_2") (pintype "passive"))
      (node (ref "U$1") (pin "P$1") (pinfunction "P$1_P$1") (pintype "bidirectional"))
    )
    (net (code "34") (name "Net-(Q3-G)") (class "Default")
      (node (ref "Q3") (pin "1") (pinfunction "G_1") (pintype "passive"))
      (node (ref "R1") (pin "1") (pinfunction "1_1") (pintype "passive"))
    )
    (net (code "35") (name "Net-(Q3-S)") (class "Default")
      (node (ref "LED2") (pin "C") (pinfunction "C_C") (pintype "passive"))
      (node (ref "Q3") (pin "2") (pinfunction "S_2") (pintype "passive"))
      (node (ref "R4") (pin "1") (pinfunction "1_1") (pintype "passive"))
      (node (ref "U$11") (pin "2") (pinfunction "2_2") (pintype "bidirectional"))
      (node (ref "U$2") (pin "P$2") (pinfunction "P$2_P$2") (pintype "bidirectional"))
    )
    (net (code "36") (name "Net-(Q4-D)") (class "Default")
      (node (ref "Q4") (pin "3") (pinfunction "D_3") (pintype "passive"))
      (node (ref "R17") (pin "2") (pinfunction "2_2") (pintype "passive"))
      (node (ref "U$2") (pin "P$1") (pinfunction "P$1_P$1") (pintype "bidirectional"))
    )
    (net (code "37") (name "Net-(Q4-G)") (class "Default")
      (node (ref "Q4") (pin "1") (pinfunction "G_1") (pintype "passive"))
      (node (ref "R2") (pin "1") (pinfunction "1_1") (pintype "passive"))
    )
    (net (code "38") (name "Net-(Q4-S)") (class "Default")
      (node (ref "LED3") (pin "C") (pinfunction "C_C") (pintype "passive"))
      (node (ref "Q4") (pin "2") (pinfunction "S_2") (pintype "passive"))
      (node (ref "R5") (pin "1") (pinfunction "1_1") (pintype "passive"))
      (node (ref "SJ8") (pin "2") (pinfunction "2_2") (pintype "passive"))
      (node (ref "U$11") (pin "3") (pinfunction "3_3") (pintype "bidirectional"))
      (node (ref "U$3") (pin "P$2") (pinfunction "P$2_P$2") (pintype "bidirectional"))
    )
    (net (code "39") (name "Net-(Q5-D)") (class "Default")
      (node (ref "Q5") (pin "3") (pinfunction "D_3") (pintype "passive"))
      (node (ref "R18") (pin "2") (pinfunction "2_2") (pintype "passive"))
      (node (ref "U$3") (pin "P$1") (pinfunction "P$1_P$1") (pintype "bidirectional"))
    )
    (net (code "40") (name "Net-(Q5-G)") (class "Default")
      (node (ref "Q5") (pin "1") (pinfunction "G_1") (pintype "passive"))
      (node (ref "R3") (pin "1") (pinfunction "1_1") (pintype "passive"))
    )
    (net (code "41") (name "Net-(Q5-S)") (class "Default")
      (node (ref "LED4") (pin "C") (pinfunction "C_C") (pintype "passive"))
      (node (ref "Q5") (pin "2") (pinfunction "S_2") (pintype "passive"))
      (node (ref "R6") (pin "1") (pinfunction "1_1") (pintype "passive"))
      (node (ref "SJ7") (pin "2") (pinfunction "2_2") (pintype "passive"))
      (node (ref "SJ8") (pin "1") (pinfunction "1_1") (pintype "passive"))
      (node (ref "U$11") (pin "4") (pinfunction "4_4") (pintype "bidirectional"))
      (node (ref "U$8") (pin "P$2") (pinfunction "P$2_P$2") (pintype "bidirectional"))
    )
    (net (code "42") (name "Net-(Q7-D)") (class "Default")
      (node (ref "Q7") (pin "3") (pinfunction "D_3") (pintype "passive"))
      (node (ref "Q9") (pin "4") (pinfunction "GATE_4") (pintype "bidirectional"))
      (node (ref "R25") (pin "1") (pinfunction "1_1") (pintype "passive"))
    )
    (net (code "43") (name "Net-(Q11-D)") (class "Default")
      (node (ref "Q11") (pin "3") (pinfunction "D_3") (pintype "passive"))
      (node (ref "R37") (pin "2") (pinfunction "2_2") (pintype "passive"))
      (node (ref "U$8") (pin "P$1") (pinfunction "P$1_P$1") (pintype "bidirectional"))
    )
    (net (code "44") (name "Net-(Q11-G)") (class "Default")
      (node (ref "Q11") (pin "1") (pinfunction "G_1") (pintype "passive"))
      (node (ref "R36") (pin "1") (pinfunction "1_1") (pintype "passive"))
    )
    (net (code "45") (name "Net-(Q11-S)") (class "Default")
      (node (ref "LED5") (pin "C") (pinfunction "C_C") (pintype "passive"))
      (node (ref "Q11") (pin "2") (pinfunction "S_2") (pintype "passive"))
      (node (ref "R38") (pin "1") (pinfunction "1_1") (pintype "passive"))
      (node (ref "SJ6") (pin "2") (pinfunction "2_2") (pintype "passive"))
      (node (ref "SJ7") (pin "1") (pinfunction "1_1") (pintype "passive"))
      (node (ref "U$11") (pin "5") (pinfunction "5_5") (pintype "bidirectional"))
      (node (ref "U$9") (pin "P$2") (pinfunction "P$2_P$2") (pintype "bidirectional"))
    )
    (net (code "46") (name "Net-(Q12-D)") (class "Default")
      (node (ref "Q12") (pin "3") (pinfunction "D_3") (pintype "passive"))
      (node (ref "R40") (pin "2") (pinfunction "2_2") (pintype "passive"))
      (node (ref "U$9") (pin "P$1") (pinfunction "P$1_P$1") (pintype "bidirectional"))
    )
    (net (code "47") (name "Net-(Q12-G)") (class "Default")
      (node (ref "Q12") (pin "1") (pinfunction "G_1") (pintype "passive"))
      (node (ref "R39") (pin "1") (pinfunction "1_1") (pintype "passive"))
    )
    (net (code "48") (name "Net-(Q12-S)") (class "Default")
      (node (ref "LED6") (pin "C") (pinfunction "C_C") (pintype "passive"))
      (node (ref "Q12") (pin "2") (pinfunction "S_2") (pintype "passive"))
      (node (ref "R43") (pin "1") (pinfunction "1_1") (pintype "passive"))
      (node (ref "SJ5") (pin "2") (pinfunction "2_2") (pintype "passive"))
      (node (ref "SJ6") (pin "1") (pinfunction "1_1") (pintype "passive"))
      (node (ref "U$10") (pin "P$2") (pinfunction "P$2_P$2") (pintype "bidirectional"))
      (node (ref "U$11") (pin "6") (pinfunction "6_6") (pintype "bidirectional"))
    )
    (net (code "49") (name "Net-(Q13-D)") (class "Default")
      (node (ref "Q13") (pin "3") (pinfunction "D_3") (pintype "passive"))
      (node (ref "R42") (pin "2") (pinfunction "2_2") (pintype "passive"))
      (node (ref "U$10") (pin "P$1") (pinfunction "P$1_P$1") (pintype "bidirectional"))
    )
    (net (code "50") (name "Net-(Q13-G)") (class "Default")
      (node (ref "Q13") (pin "1") (pinfunction "G_1") (pintype "passive"))
      (node (ref "R41") (pin "1") (pinfunction "1_1") (pintype "passive"))
    )
    (net (code "51") (name "Net-(Q13-S)") (class "Default")
      (node (ref "Q13") (pin "2") (pinfunction "S_2") (pintype "passive"))
      (node (ref "R44") (pin "1") (pinfunction "1_1") (pintype "passive"))
      (node (ref "R7") (pin "1") (pinfunction "1_1") (pintype "passive"))
      (node (ref "R8") (pin "1") (pinfunction "1_1") (pintype "passive"))
      (node (ref "SJ5") (pin "1") (pinfunction "1_1") (pintype "passive"))
      (node (ref "U$11") (pin "7") (pinfunction "7_7") (pintype "bidirectional"))
    )
    (net (code "52") (name "Net-(Q14-GATE)") (class "Default")
      (node (ref "Q14") (pin "4") (pinfunction "GATE_4") (pintype "bidirectional"))
      (node (ref "U$12") (pin "P$5") (pinfunction "GATE_P$5") (pintype "bidirectional"))
    )
    (net (code "53") (name "Net-(U$5-A1)") (class "Default")
      (node (ref "A1") (pin "2") (pinfunction "2_2") (pintype "passive"))
      (node (ref "U$5") (pin "38") (pinfunction "A1_38") (pintype "bidirectional"))
    )
    (net (code "54") (name "Net-(U$5-A2)") (class "Default")
      (node (ref "A2") (pin "2") (pinfunction "2_2") (pintype "passive"))
      (node (ref "U$5") (pin "39") (pinfunction "A2_39") (pintype "bidirectional"))
    )
    (net (code "55") (name "Net-(U$5-A3)") (class "Default")
      (node (ref "A3") (pin "2") (pinfunction "2_2") (pintype "passive"))
      (node (ref "U$5") (pin "40") (pinfunction "A3_40") (pintype "bidirectional"))
    )
    (net (code "56") (name "Net-(U$5-AO)") (class "Default")
      (node (ref "A0") (pin "2") (pinfunction "2_2") (pintype "passive"))
      (node (ref "U$5") (pin "37") (pinfunction "AO_37") (pintype "bidirectional"))
    )
    (net (code "57") (name "Net-(U$5-C10)") (class "Default")
      (node (ref "R7") (pin "2") (pinfunction "2_2") (pintype "passive"))
      (node (ref "SJ1") (pin "2") (pinfunction "2_2") (pintype "passive"))
      (node (ref "U$5") (pin "10") (pinfunction "C8_10") (pintype "bidirectional"))
      (node (ref "U$5") (pin "12") (pinfunction "C7_12") (pintype "bidirectional"))
      (node (ref "U$5") (pin "2") (pinfunction "C12_2") (pintype "bidirectional"))
      (node (ref "U$5") (pin "4") (pinfunction "C11_4") (pintype "bidirectional"))
      (node (ref "U$5") (pin "6") (pinfunction "C10_6") (pintype "bidirectional"))
      (node (ref "U$5") (pin "8") (pinfunction "C9_8") (pintype "bidirectional"))
    )
    (net (code "58") (name "Net-(U$5-GPIO1)") (class "Default")
      (node (ref "R23") (pin "2") (pinfunction "2_2") (pintype "passive"))
      (node (ref "U$5") (pin "35") (pinfunction "GPIO1_35") (pintype "bidirectional"))
    )
    (net (code "59") (name "Net-(U$5-GPIO2)") (class "Default")
      (node (ref "R22") (pin "2") (pinfunction "2_2") (pintype "passive"))
      (node (ref "U$5") (pin "36") (pinfunction "GPIO2_36") (pintype "bidirectional"))
    )
    (net (code "60") (name "Net-(U$5-S1)") (class "Default")
      (node (ref "R1") (pin "2") (pinfunction "2_2") (pintype "passive"))
      (node (ref "U$5") (pin "25") (pinfunction "S1_25") (pintype "bidirectional"))
    )
    (net (code "61") (name "Net-(U$5-S2)") (class "Default")
      (node (ref "R2") (pin "2") (pinfunction "2_2") (pintype "passive"))
      (node (ref "U$5") (pin "23") (pinfunction "S2_23") (pintype "bidirectional"))
    )
    (net (code "62") (name "Net-(U$5-S3)") (class "Default")
      (node (ref "R3") (pin "2") (pinfunction "2_2") (pintype "passive"))
      (node (ref "U$5") (pin "21") (pinfunction "S3_21") (pintype "bidirectional"))
    )
    (net (code "63") (name "Net-(U$5-S4)") (class "Default")
      (node (ref "R36") (pin "2") (pinfunction "2_2") (pintype "passive"))
      (node (ref "U$5") (pin "19") (pinfunction "S4_19") (pintype "bidirectional"))
    )
    (net (code "64") (name "Net-(U$5-S5)") (class "Default")
      (node (ref "R39") (pin "2") (pinfunction "2_2") (pintype "passive"))
      (node (ref "U$5") (pin "17") (pinfunction "S5_17") (pintype "bidirectional"))
    )
    (net (code "65") (name "Net-(U$5-S6)") (class "Default")
      (node (ref "R41") (pin "2") (pinfunction "2_2") (pintype "passive"))
      (node (ref "U$5") (pin "15") (pinfunction "S6_15") (pintype "bidirectional"))
    )
    (net (code "66") (name "Net-(U$5-TOS)") (class "Default")
      (node (ref "TOS") (pin "2") (pinfunction "2_2") (pintype "passive"))
      (node (ref "U$5") (pin "32") (pinfunction "TOS_32") (pintype "bidirectional"))
    )
    (net (code "67") (name "Net-(U$5-VREF)") (class "Default")
      (node (ref "C6") (pin "2") (pinfunction "2_2") (pintype "passive"))
      (node (ref "U$5") (pin "30") (pinfunction "VREF_30") (pintype "bidirectional"))
    )
    (net (code "68") (name "Net-(U$5-WDTB)") (class "Default")
      (node (ref "R24") (pin "2") (pinfunction "2_2") (pintype "passive"))
      (node (ref "U$5") (pin "34") (pinfunction "WDTB_34") (pintype "bidirectional"))
    )
    (net (code "69") (name "Net-(U$6-AREF)") (class "Default")
      (node (ref "C14") (pin "2") (pinfunction "2_2") (pintype "passive"))
      (node (ref "U$6") (pin "42") (pinfunction "AREF_42") (pintype "bidirectional"))
    )
    (net (code "70") (name "Net-(U$6-D+)") (class "Default")
      (node (ref "R29") (pin "1") (pinfunction "1_1") (pintype "passive"))
      (node (ref "U$6") (pin "4") (pinfunction "D+_4") (pintype "bidirectional"))
    )
    (net (code "71") (name "Net-(U$6-D-)") (class "Default")
      (node (ref "R30") (pin "1") (pinfunction "1_1") (pintype "passive"))
      (node (ref "U$6") (pin "3") (pinfunction "D-_3") (pintype "bidirectional"))
    )
    (net (code "72") (name "Net-(U$6-PE2{slash}~{HWB})") (class "Default")
      (node (ref "R35") (pin "2") (pinfunction "2_2") (pintype "passive"))
      (node (ref "U$6") (pin "33") (pinfunction "PE2/~{HWB}_33") (pintype "bidirectional"))
    )
    (net (code "73") (name "Net-(U$6-UCAP)") (class "Default")
      (node (ref "C15") (pin "2") (pinfunction "2_2") (pintype "passive"))
      (node (ref "U$6") (pin "6") (pinfunction "UCAP_6") (pintype "bidirectional"))
    )
    (net (code "74") (name "Net-(U$6-VBUS)") (class "Default")
      (node (ref "F1") (pin "2") (pinfunction "2_2") (pintype "bidirectional"))
      (node (ref "U$6") (pin "7") (pinfunction "VBUS_7") (pintype "bidirectional"))
    )
    (net (code "75") (name "Net-(U$6-XTAL1)") (class "Default")
      (node (ref "C17") (pin "1") (pinfunction "1_1") (pintype "passive"))
      (node (ref "R32") (pin "1") (pinfunction "1_1") (pintype "passive"))
      (node (ref "U$6") (pin "17") (pinfunction "XTAL1_17") (pintype "bidirectional"))
      (node (ref "U$7") (pin "IN") (pinfunction "IN_IN") (pintype "bidirectional"))
    )
    (net (code "76") (name "Net-(U$6-XTAL2)") (class "Default")
      (node (ref "C16") (pin "2") (pinfunction "2_2") (pintype "passive"))
      (node (ref "R32") (pin "2") (pinfunction "2_2") (pintype "passive"))
      (node (ref "U$6") (pin "16") (pinfunction "XTAL2_16") (pintype "bidirectional"))
      (node (ref "U$7") (pin "OUT") (pinfunction "OUT_OUT") (pintype "bidirectional"))
    )
    (net (code "77") (name "Net-(U$12-SNSE)") (class "Default")
      (node (ref "Q14") (pin "1") (pinfunction "SOURCE_1") (pintype "bidirectional"))
      (node (ref "Q14") (pin "2") (pinfunction "SOURCE_2") (pintype "bidirectional"))
      (node (ref "Q14") (pin "3") (pinfunction "SOURCE_3") (pintype "bidirectional"))
      (node (ref "Q9") (pin "1") (pinfunction "SOURCE_1") (pintype "bidirectional"))
      (node (ref "Q9") (pin "2") (pinfunction "SOURCE_2") (pintype "bidirectional"))
      (node (ref "Q9") (pin "3") (pinfunction "SOURCE_3") (pintype "bidirectional"))
      (node (ref "R25") (pin "2") (pinfunction "2_2") (pintype "passive"))
      (node (ref "U$12") (pin "P$6") (pinfunction "SNSE_P$6") (pintype "bidirectional"))
    )
    (net (code "78") (name "PWR") (class "Default")
      (node (ref "J1") (pin "D6") (pinfunction "*D6_D6") (pintype "bidirectional"))
      (node (ref "Q2") (pin "1") (pinfunction "G_1") (pintype "passive"))
      (node (ref "R10") (pin "2") (pinfunction "2_2") (pintype "passive"))
      (node (ref "U$6") (pin "27") (pinfunction "PD7(ADC10)_27") (pintype "bidirectional"))
    )
    (net (code "79") (name "RESET") (class "Default")
      (node (ref "JP1") (pin "5") (pinfunction "5_5") (pintype "passive"))
      (node (ref "R28") (pin "1") (pinfunction "1_1") (pintype "passive"))
      (node (ref "U$6") (pin "13") (pinfunction "~{RESET}_13") (pintype "bidirectional"))
    )
    (net (code "80") (name "SCK") (class "Default")
      (node (ref "J1") (pin "D13") (pinfunction "D13_D13") (pintype "bidirectional"))
      (node (ref "JP1") (pin "3") (pinfunction "3_3") (pintype "passive"))
      (node (ref "U$5") (pin "41") (pinfunction "SCKI_41") (pintype "bidirectional"))
      (node (ref "U$6") (pin "9") (pinfunction "PB1(SCK)_9") (pintype "bidirectional"))
    )
    (net (code "81") (name "SCL") (class "Default")
      (node (ref "J1") (pin "SCL") (pinfunction "SCL_SCL") (pintype "bidirectional"))
      (node (ref "R15") (pin "1") (pinfunction "1_1") (pintype "passive"))
      (node (ref "U$13") (pin "P$8") (pinfunction "P$8_P$8") (pintype "bidirectional"))
      (node (ref "U$6") (pin "18") (pinfunction "PD0(SCL)_18") (pintype "bidirectional"))
    )
    (net (code "82") (name "SDA") (class "Default")
      (node (ref "J1") (pin "SDA") (pinfunction "SDA_SDA") (pintype "bidirectional"))
      (node (ref "R14") (pin "1") (pinfunction "1_1") (pintype "passive"))
      (node (ref "U$13") (pin "P$7") (pinfunction "P$7_P$7") (pintype "bidirectional"))
      (node (ref "U$6") (pin "19") (pinfunction "PD1(SDA)_19") (pintype "bidirectional"))
    )
    (net (code "83") (name "SS") (class "Default")
      (node (ref "J1") (pin "D10") (pinfunction "*D10_D10") (pintype "bidirectional"))
      (node (ref "U$5") (pin "44") (pinfunction "CSBI_44") (pintype "bidirectional"))
      (node (ref "U$6") (pin "8") (pinfunction "PB0(SS)_8") (pintype "bidirectional"))
    )
    (net (code "84") (name "START{slash}E-STOP1") (class "Default")
      (node (ref "Q10") (pin "G") (pinfunction "G_G") (pintype "passive"))
      (node (ref "R26") (pin "1") (pinfunction "1_1") (pintype "passive"))
      (node (ref "U$13") (pin "P$4") (pinfunction "P$4_P$4") (pintype "bidirectional"))
    )
    (net (code "85") (name "UGND") (class "Default")
      (node (ref "C15") (pin "1") (pinfunction "1_1") (pintype "passive"))
      (node (ref "L1") (pin "2") (pinfunction "2_2") (pintype "passive"))
      (node (ref "R31") (pin "1") (pinfunction "1_1") (pintype "passive"))
      (node (ref "U$6") (pin "5") (pinfunction "UGND_5") (pintype "bidirectional"))
      (node (ref "X1") (pin "5") (pinfunction "5_5") (pintype "passive"))
    )
    (net (code "86") (name "VREG") (class "Default")
      (node (ref "A0") (pin "1") (pinfunction "1_1") (pintype "passive"))
      (node (ref "A1") (pin "1") (pinfunction "1_1") (pintype "passive"))
      (node (ref "A2") (pin "1") (pinfunction "1_1") (pintype "passive"))
      (node (ref "A3") (pin "1") (pinfunction "1_1") (pintype "passive"))
      (node (ref "C4") (pin "1") (pinfunction "1_1") (pintype "passive"))
      (node (ref "R11") (pin "2") (pinfunction "2_2") (pintype "passive"))
      (node (ref "TOS") (pin "1") (pinfunction "1_1") (pintype "passive"))
      (node (ref "U$5") (pin "31") (pinfunction "VREG_31") (pintype "bidirectional"))
    )
    (net (code "87") (name "VTEMP1") (class "Default")
      (node (ref "C7") (pin "2") (pinfunction "2_2") (pintype "passive"))
      (node (ref "R11") (pin "1") (pinfunction "1_1") (pintype "passive"))
      (node (ref "U$13") (pin "P$6") (pinfunction "P$6_P$6") (pintype "bidirectional"))
      (node (ref "U$5") (pin "28") (pinfunction "VTEMP1_28") (pintype "bidirectional"))
    )
    (net (code "88") (name "unconnected-(J1-*D3-PadD3)") (class "Default")
      (node (ref "J1") (pin "D3") (pinfunction "*D3_D3") (pintype "bidirectional"))
    )
    (net (code "89") (name "unconnected-(J1-*D5-PadD5)") (class "Default")
      (node (ref "J1") (pin "D5") (pinfunction "*D5_D5") (pintype "bidirectional"))
    )
    (net (code "90") (name "unconnected-(J1-Pad3.3V)") (class "Default")
      (node (ref "J1") (pin "3.3V") (pinfunction "3.3V_3.3V") (pintype "bidirectional"))
    )
    (net (code "91") (name "unconnected-(J1-PadA0)") (class "Default")
      (node (ref "J1") (pin "A0") (pinfunction "A0_A0") (pintype "bidirectional"))
    )
    (net (code "92") (name "unconnected-(J1-PadA1)") (class "Default")
      (node (ref "J1") (pin "A1") (pinfunction "A1_A1") (pintype "bidirectional"))
    )
    (net (code "93") (name "unconnected-(J1-PadA2)") (class "Default")
      (node (ref "J1") (pin "A2") (pinfunction "A2_A2") (pintype "bidirectional"))
    )
    (net (code "94") (name "unconnected-(J1-PadA3)") (class "Default")
      (node (ref "J1") (pin "A3") (pinfunction "A3_A3") (pintype "bidirectional"))
    )
    (net (code "95") (name "unconnected-(J1-PadA4)") (class "Default")
      (node (ref "J1") (pin "A4") (pinfunction "A4_A4") (pintype "bidirectional"))
    )
    (net (code "96") (name "unconnected-(J1-PadA5)") (class "Default")
      (node (ref "J1") (pin "A5") (pinfunction "A5_A5") (pintype "bidirectional"))
    )
    (net (code "97") (name "unconnected-(J1-PadAREF)") (class "Default")
      (node (ref "J1") (pin "AREF") (pinfunction "AREF_AREF") (pintype "bidirectional"))
    )
    (net (code "98") (name "unconnected-(J1-PadD2)") (class "Default")
      (node (ref "J1") (pin "D2") (pinfunction "D2_D2") (pintype "bidirectional"))
    )
    (net (code "99") (name "unconnected-(J1-PadD4)") (class "Default")
      (node (ref "J1") (pin "D4") (pinfunction "D4_D4") (pintype "bidirectional"))
    )
    (net (code "100") (name "unconnected-(J1-PadIOREF)") (class "Default")
      (node (ref "J1") (pin "IOREF") (pinfunction "IOREF_IOREF") (pintype "bidirectional"))
    )
    (net (code "101") (name "unconnected-(J1-PadRES)") (class "Default")
      (node (ref "J1") (pin "RES") (pinfunction "RES_RES") (pintype "bidirectional"))
    )
    (net (code "102") (name "unconnected-(J1-PadRX)") (class "Default")
      (node (ref "J1") (pin "RX") (pinfunction "RX_RX") (pintype "bidirectional"))
    )
    (net (code "103") (name "unconnected-(J1-PadTX)") (class "Default")
      (node (ref "J1") (pin "TX") (pinfunction "TX_TX") (pintype "bidirectional"))
    )
    (net (code "104") (name "unconnected-(J1-PadVIN)") (class "Default")
      (node (ref "J1") (pin "VIN") (pinfunction "VIN_VIN") (pintype "bidirectional"))
    )
    (net (code "105") (name "unconnected-(U$5-NC-Pad27)") (class "Default")
      (node (ref "U$5") (pin "27") (pinfunction "NC_27") (pintype "bidirectional"))
    )
    (net (code "106") (name "unconnected-(U$5-NC1-Pad33)") (class "Default")
      (node (ref "U$5") (pin "33") (pinfunction "NC1_33") (pintype "bidirectional"))
    )
    (net (code "107") (name "unconnected-(U$5-S7-Pad13)") (class "Default")
      (node (ref "U$5") (pin "13") (pinfunction "S7_13") (pintype "bidirectional"))
    )
    (net (code "108") (name "unconnected-(U$5-S8-Pad11)") (class "Default")
      (node (ref "U$5") (pin "11") (pinfunction "S8_11") (pintype "bidirectional"))
    )
    (net (code "109") (name "unconnected-(U$5-S9-Pad9)") (class "Default")
      (node (ref "U$5") (pin "9") (pinfunction "S9_9") (pintype "bidirectional"))
    )
    (net (code "110") (name "unconnected-(U$5-S10-Pad7)") (class "Default")
      (node (ref "U$5") (pin "7") (pinfunction "S10_7") (pintype "bidirectional"))
    )
    (net (code "111") (name "unconnected-(U$5-S11-Pad5)") (class "Default")
      (node (ref "U$5") (pin "5") (pinfunction "S11_5") (pintype "bidirectional"))
    )
    (net (code "112") (name "unconnected-(U$5-S12-Pad3)") (class "Default")
      (node (ref "U$5") (pin "3") (pinfunction "S12_3") (pintype "bidirectional"))
    )
    (net (code "113") (name "unconnected-(U$5-VTEMP2-Pad29)") (class "Default")
      (node (ref "U$5") (pin "29") (pinfunction "VTEMP2_29") (pintype "bidirectional"))
    )
    (net (code "114") (name "unconnected-(U$6-PB6(ADC13)-Pad30)") (class "Default")
      (node (ref "U$6") (pin "30") (pinfunction "PB6(ADC13)_30") (pintype "bidirectional"))
    )
    (net (code "115") (name "unconnected-(U$6-PB7-Pad12)") (class "Default")
      (node (ref "U$6") (pin "12") (pinfunction "PB7_12") (pintype "bidirectional"))
    )
    (net (code "116") (name "unconnected-(U$6-PC6-Pad31)") (class "Default")
      (node (ref "U$6") (pin "31") (pinfunction "PC6_31") (pintype "bidirectional"))
    )
    (net (code "117") (name "unconnected-(U$6-PD2(RX)-Pad20)") (class "Default")
      (node (ref "U$6") (pin "20") (pinfunction "PD2(RX)_20") (pintype "bidirectional"))
    )
    (net (code "118") (name "unconnected-(U$6-PD3(TX)-Pad21)") (class "Default")
      (node (ref "U$6") (pin "21") (pinfunction "PD3(TX)_21") (pintype "bidirectional"))
    )
    (net (code "119") (name "unconnected-(U$6-PD4(ADC8)-Pad25)") (class "Default")
      (node (ref "U$6") (pin "25") (pinfunction "PD4(ADC8)_25") (pintype "bidirectional"))
    )
    (net (code "120") (name "unconnected-(U$6-PD5-Pad22)") (class "Default")
      (node (ref "U$6") (pin "22") (pinfunction "PD5_22") (pintype "bidirectional"))
    )
    (net (code "121") (name "unconnected-(U$6-PD6(ADC9)-Pad26)") (class "Default")
      (node (ref "U$6") (pin "26") (pinfunction "PD6(ADC9)_26") (pintype "bidirectional"))
    )
    (net (code "122") (name "unconnected-(U$6-PF0(ADC0)-Pad41)") (class "Default")
      (node (ref "U$6") (pin "41") (pinfunction "PF0(ADC0)_41") (pintype "bidirectional"))
    )
    (net (code "123") (name "unconnected-(U$6-PF1(ADC1)-Pad40)") (class "Default")
      (node (ref "U$6") (pin "40") (pinfunction "PF1(ADC1)_40") (pintype "bidirectional"))
    )
    (net (code "124") (name "unconnected-(U$6-PF4(ADC4)-Pad39)") (class "Default")
      (node (ref "U$6") (pin "39") (pinfunction "PF4(ADC4)_39") (pintype "bidirectional"))
    )
    (net (code "125") (name "unconnected-(U$6-PF5(ADC5)-Pad38)") (class "Default")
      (node (ref "U$6") (pin "38") (pinfunction "PF5(ADC5)_38") (pintype "bidirectional"))
    )
    (net (code "126") (name "unconnected-(U$6-PF6(ADC6)-Pad37)") (class "Default")
      (node (ref "U$6") (pin "37") (pinfunction "PF6(ADC6)_37") (pintype "bidirectional"))
    )
    (net (code "127") (name "unconnected-(U$6-PF7(ADC7)-Pad36)") (class "Default")
      (node (ref "U$6") (pin "36") (pinfunction "PF7(ADC7)_36") (pintype "bidirectional"))
    )
    (net (code "128") (name "unconnected-(X1-Pad4)") (class "Default")
      (node (ref "X1") (pin "4") (pinfunction "4_4") (pintype "passive"))
    )
  )
)
